# habanero-32m.net
KiCad netlist of a schematic drawn in EAGLE
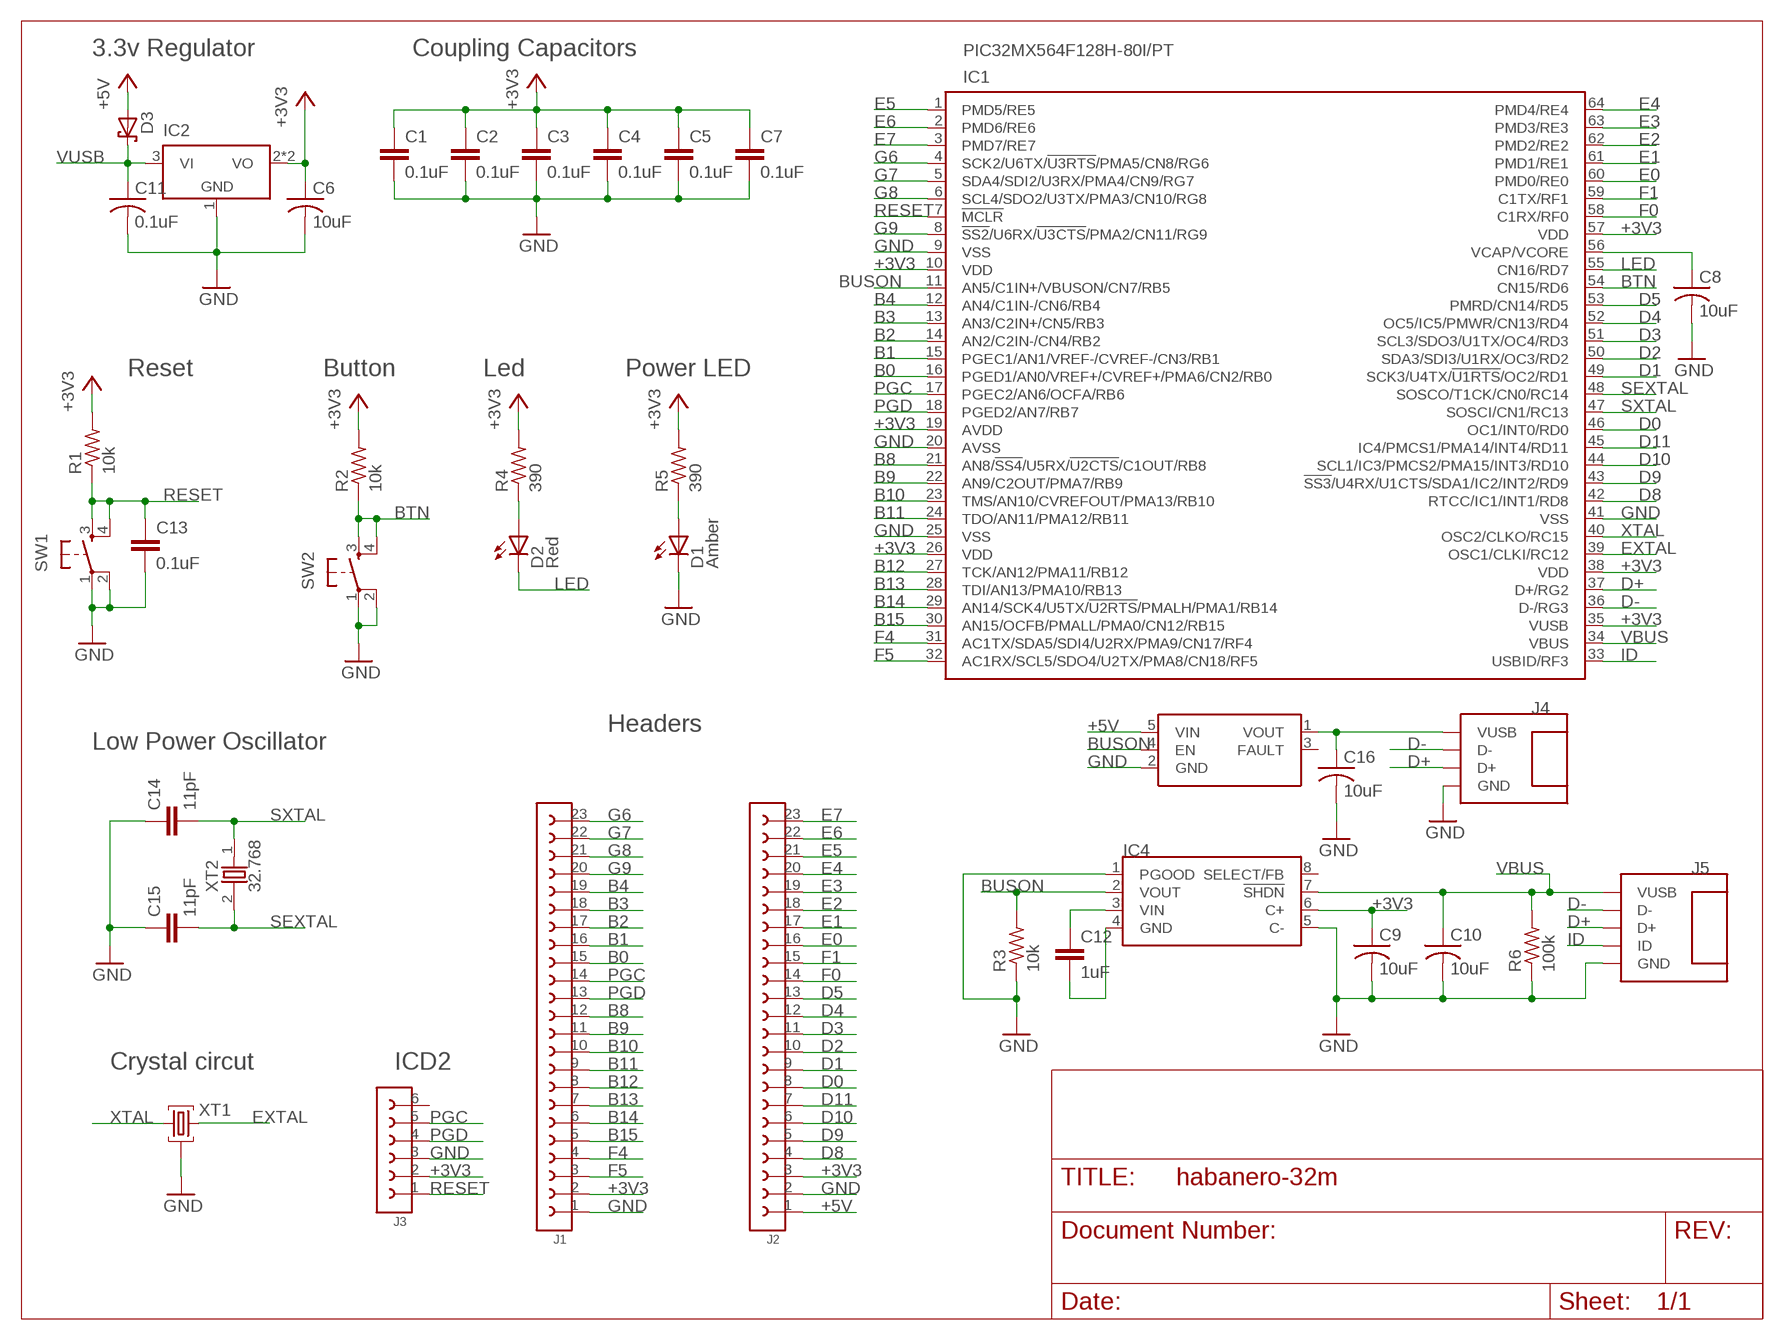
[diagram p0: schematic, sheet 1]

(export (version "E")
  (design (tool "Eeschema 10.0.6"))
  (components
    (comp (ref "C1")
      (value "0.1uF")
      (footprint "eagle-import:CAPC0603")
      (fields (field (name "MANUFACTURER") "KEMET"))
      (libsource (lib "eagle-import") (part "C?CVAC0603104Z3"))
    )
    (comp (ref "C2")
      (value "0.1uF")
      (footprint "eagle-import:CAPC0603")
      (fields (field (name "MANUFACTURER") "KEMET"))
      (libsource (lib "eagle-import") (part "C?CVAC0603104Z3"))
    )
    (comp (ref "C3")
      (value "0.1uF")
      (footprint "eagle-import:CAPC0603")
      (fields (field (name "MANUFACTURER") "KEMET"))
      (libsource (lib "eagle-import") (part "C?CVAC0603104Z3"))
    )
    (comp (ref "C4")
      (value "0.1uF")
      (footprint "eagle-import:CAPC0603")
      (fields (field (name "MANUFACTURER") "KEMET"))
      (libsource (lib "eagle-import") (part "C?CVAC0603104Z3"))
    )
    (comp (ref "C5")
      (value "0.1uF")
      (footprint "eagle-import:CAPC0603")
      (fields (field (name "MANUFACTURER") "KEMET"))
      (libsource (lib "eagle-import") (part "C?CVAC0603104Z3"))
    )
    (comp (ref "C6")
      (value "10uF")
      (footprint "eagle-import:CAPMP3216-18")
      (fields (field (name "MANUFACTURER") "KEMET"))
      (libsource (lib "eagle-import") (part "T491?A106K016AT"))
    )
    (comp (ref "C7")
      (value "0.1uF")
      (footprint "eagle-import:CAPC0603")
      (fields (field (name "MANUFACTURER") "KEMET"))
      (libsource (lib "eagle-import") (part "C?CVAC0603104Z3"))
    )
    (comp (ref "C8")
      (value "10uF")
      (footprint "eagle-import:CAPMP3216-18")
      (fields (field (name "MANUFACTURER") "KEMET"))
      (libsource (lib "eagle-import") (part "T491?A106K016AT"))
    )
    (comp (ref "C9")
      (value "10uF")
      (footprint "eagle-import:CAPMP3216-18")
      (fields (field (name "MANUFACTURER") "KEMET"))
      (libsource (lib "eagle-import") (part "T491?A106K016AT"))
    )
    (comp (ref "C10")
      (value "10uF")
      (footprint "eagle-import:CAPMP3216-18")
      (fields (field (name "MANUFACTURER") "KEMET"))
      (libsource (lib "eagle-import") (part "T491?A106K016AT"))
    )
    (comp (ref "C11")
      (value "0.1uF")
      (footprint "eagle-import:CAPMP3216-18")
      (fields (field (name "MANUFACTURER") "KEMET"))
      (libsource (lib "eagle-import") (part "T491?A104K050AT"))
    )
    (comp (ref "C12")
      (value "1uF")
      (footprint "eagle-import:CAPC0805")
      (fields (field (name "EAGLEUP") "CAPC0805"))
      (libsource (lib "eagle-import") (part "C?CRAC0805105K4"))
    )
    (comp (ref "C13")
      (value "0.1uF")
      (footprint "eagle-import:CAPC0603")
      (fields (field (name "MANUFACTURER") "KEMET"))
      (libsource (lib "eagle-import") (part "C?CVAC0603104Z3"))
    )
    (comp (ref "C14")
      (value "11pF")
      (footprint "eagle-import:CAPC0603")
      (fields (field (name "MANUFACTURER") "KEMET"))
      (libsource (lib "eagle-import") (part "C?CGAC0603110J5"))
    )
    (comp (ref "C15")
      (value "11pF")
      (footprint "eagle-import:CAPC0603")
      (fields (field (name "MANUFACTURER") "KEMET"))
      (libsource (lib "eagle-import") (part "C?CGAC0603110J5"))
    )
    (comp (ref "C16")
      (value "10uF")
      (footprint "eagle-import:CAPMP3216-18")
      (description "Capacitores de tantalio - SMD sólido 16volt 10uF 10% Lead Free")
      (fields
        (field (name "MANUFACTURER") "KEMET")
        (field (name "AVRG-PRICE") "0.18")
        (field (name "DIGIKEY") "399-8269-2-ND")
        (field (name "EAGLEUP") "CAPMP3216-18")
        (field (name "MANUFACTURER_1") "KEMET")
        (field (name "MOUSER") "80-T491A106K016")
        (field (name "OCTOPART-LINK") "http://octopart.com/t491a106k016at-kemet-145880")
      )
      (libsource (lib "eagle-import") (part "T491?A106K016AT"))
    )
    (comp (ref "D1")
      (value "Amber")
      (footprint "eagle-import:D0805")
      (libsource (lib "eagle-import") (part "SM0805AC"))
    )
    (comp (ref "D2")
      (value "Red")
      (footprint "eagle-import:D0805")
      (libsource (lib "eagle-import") (part "SM0805HC"))
    )
    (comp (ref "D3")
      (value "MBR0530T1G")
      (footprint "eagle-import:SOT123160X270-2N")
      (fields (field (name "EAGLEUP") "SOD123"))
      (libsource (lib "eagle-import") (part "MBR0530TG1"))
    )
    (comp (ref "IC1")
      (value "PIC32MX564F128H-80I/PT")
      (footprint "eagle-import:QFP50P1200X1200X100-64N")
      (libsource (lib "eagle-import") (part "PIC32MX5H?-80I/PT64F128"))
    )
    (comp (ref "IC2")
      (value "LD1117S33TR")
      (footprint "eagle-import:SOT230P700X180-4N")
      (fields (field (name "MANUFACTURER") "ST"))
      (libsource (lib "eagle-import") (part "LD1117?S33TR"))
    )
    (comp (ref "IC3")
      (value "SMTPS2141STR")
      (footprint "eagle-import:SOT95P280X100-5M")
      (fields (field (name "EAGLEUP") "SOT95P280X100-5N"))
      (libsource (lib "eagle-import") (part "SMTPS21?TRS41"))
    )
    (comp (ref "IC4")
      (value "MCP1253-33X50I/MS")
      (footprint "eagle-import:SOP65P490X109-8M")
      (fields (field (name "MANUFACTURER") "MICROCHIP"))
      (libsource (lib "eagle-import") (part "MCP125?I/MS3-33X50"))
    )
    (comp (ref "J1")
      (value "61302311121")
      (footprint "eagle-import:PHSP254P5842X254X1154-23S")
      (libsource (lib "eagle-import") (part "6130231?1121"))
    )
    (comp (ref "J2")
      (value "61302311121")
      (footprint "eagle-import:PHSP254P5842X254X1154-23S")
      (libsource (lib "eagle-import") (part "6130231?1121"))
    )
    (comp (ref "J3")
      (value "61300611121")
      (footprint "eagle-import:PHSP254P1524X254X1154-6S")
      (fields (field (name "MANUFACTURER") "WURTH"))
      (libsource (lib "eagle-import") (part "6130061?1121"))
    )
    (comp (ref "J4")
      (value "292303-1")
      (footprint "eagle-import:USB-A")
      (libsource (lib "eagle-import") (part "292303-?1"))
    )
    (comp (ref "J5")
      (value "1981584-1")
      (footprint "eagle-import:USB-MICRO-B")
      (libsource (lib "eagle-import") (part "1981584-1"))
    )
    (comp (ref "R1")
      (value "10k")
      (footprint "eagle-import:RESC0603")
      (libsource (lib "eagle-import") (part "CRG?0603F10K10"))
    )
    (comp (ref "R2")
      (value "10k")
      (footprint "eagle-import:RESC0603")
      (libsource (lib "eagle-import") (part "CRG?0603F10K10"))
    )
    (comp (ref "R3")
      (value "10k")
      (footprint "eagle-import:RESC0603")
      (libsource (lib "eagle-import") (part "CRG?0603F10K10"))
    )
    (comp (ref "R4")
      (value "390")
      (footprint "eagle-import:RESC0603")
      (libsource (lib "eagle-import") (part "CRG?0603F390R"))
    )
    (comp (ref "R5")
      (value "390")
      (footprint "eagle-import:RESC0603")
      (libsource (lib "eagle-import") (part "CRG?0603F390R"))
    )
    (comp (ref "R6")
      (value "100k")
      (footprint "eagle-import:RESC0603")
      (libsource (lib "eagle-import") (part "CRG?0603F100K"))
    )
    (comp (ref "SW1")
      (value "TL3301NF160QJ")
      (footprint "eagle-import:TACT600X600-4J")
      (fields (field (name "MANUFACTURER") "E-SWITCH"))
      (libsource (lib "eagle-import") (part "TL3301?JNF160Q"))
    )
    (comp (ref "SW2")
      (value "TL3301NF160QJ")
      (footprint "eagle-import:TACT600X600-4J")
      (fields (field (name "MANUFACTURER") "E-SWITCH"))
      (libsource (lib "eagle-import") (part "TL3301?JNF160Q"))
    )
    (comp (ref "XT1")
      (value "AWSCR-12.00CR-C")
      (footprint "eagle-import:CERAMIC460X200-3N")
      (fields (field (name "MANUFACTURER") "ABRACON"))
      (libsource (lib "eagle-import") (part "AWSCR-CR-C12.00"))
    )
    (comp (ref "XT2")
      (value "32.768")
      (footprint "eagle-import:CEMIC320X150-2N")
      (fields (field (name "MANUFACTURER") "ABRACON"))
      (libsource (lib "eagle-import") (part "ABS07-120-32.768KHZ-T"))
    )
  )
  (nets
    (net (code "1") (name "+3V3") (class "Default")
      (node (ref "C1") (pin "1") (pinfunction "1_1") (pintype "passive"))
      (node (ref "C2") (pin "1") (pinfunction "1_1") (pintype "passive"))
      (node (ref "C3") (pin "1") (pinfunction "1_1") (pintype "passive"))
      (node (ref "C4") (pin "1") (pinfunction "1_1") (pintype "passive"))
      (node (ref "C5") (pin "1") (pinfunction "1_1") (pintype "passive"))
      (node (ref "C6") (pin "1") (pinfunction "1_1") (pintype "passive"))
      (node (ref "C7") (pin "1") (pinfunction "1_1") (pintype "passive"))
      (node (ref "C9") (pin "1") (pinfunction "1_1") (pintype "passive"))
      (node (ref "IC1") (pin "10") (pinfunction "VDD_10") (pintype "power_in"))
      (node (ref "IC1") (pin "19") (pinfunction "AVDD_19") (pintype "power_in"))
      (node (ref "IC1") (pin "26") (pinfunction "VDD_26") (pintype "power_in"))
      (node (ref "IC1") (pin "35") (pinfunction "VUSB_35") (pintype "power_in"))
      (node (ref "IC1") (pin "38") (pinfunction "VDD_38") (pintype "power_in"))
      (node (ref "IC1") (pin "57") (pinfunction "VDD_57") (pintype "power_in"))
      (node (ref "IC2") (pin "2") (pinfunction "VO_2") (pintype "input"))
      (node (ref "IC2") (pin "4") (pinfunction "VO_4") (pintype "input"))
      (node (ref "IC4") (pin "6") (pinfunction "C+_6") (pintype "bidirectional"))
      (node (ref "J1") (pin "2") (pinfunction "2_2") (pintype "passive"))
      (node (ref "J2") (pin "3") (pinfunction "3_3") (pintype "passive"))
      (node (ref "J3") (pin "2") (pinfunction "2_2") (pintype "passive"))
      (node (ref "R1") (pin "P$2") (pinfunction "2_P$2") (pintype "passive"))
      (node (ref "R2") (pin "P$2") (pinfunction "2_P$2") (pintype "passive"))
      (node (ref "R4") (pin "P$2") (pinfunction "2_P$2") (pintype "passive"))
      (node (ref "R5") (pin "P$2") (pinfunction "2_P$2") (pintype "passive"))
    )
    (net (code "2") (name "+5V") (class "Default")
      (node (ref "D3") (pin "1") (pinfunction "A_1") (pintype "passive"))
      (node (ref "IC3") (pin "5") (pinfunction "VIN_5") (pintype "power_in"))
      (node (ref "J2") (pin "1") (pinfunction "1_1") (pintype "passive"))
    )
    (net (code "3") (name "/B0") (class "Default")
      (node (ref "IC1") (pin "16") (pinfunction "PGED1/AN0/VREF+/CVREF+/PMA6/CN2/RB0_16") (pintype "bidirectional"))
      (node (ref "J1") (pin "15") (pinfunction "15_15") (pintype "passive"))
    )
    (net (code "4") (name "/B1") (class "Default")
      (node (ref "IC1") (pin "15") (pinfunction "PGEC1/AN1/VREF-/CVREF-/CN3/RB1_15") (pintype "bidirectional"))
      (node (ref "J1") (pin "16") (pinfunction "16_16") (pintype "passive"))
    )
    (net (code "5") (name "/B2") (class "Default")
      (node (ref "IC1") (pin "14") (pinfunction "AN2/C2IN-/CN4/RB2_14") (pintype "bidirectional"))
      (node (ref "J1") (pin "17") (pinfunction "17_17") (pintype "passive"))
    )
    (net (code "6") (name "/B3") (class "Default")
      (node (ref "IC1") (pin "13") (pinfunction "AN3/C2IN+/CN5/RB3_13") (pintype "bidirectional"))
      (node (ref "J1") (pin "18") (pinfunction "18_18") (pintype "passive"))
    )
    (net (code "7") (name "/B4") (class "Default")
      (node (ref "IC1") (pin "12") (pinfunction "AN4/C1IN-/CN6/RB4_12") (pintype "bidirectional"))
      (node (ref "J1") (pin "19") (pinfunction "19_19") (pintype "passive"))
    )
    (net (code "8") (name "/B8") (class "Default")
      (node (ref "IC1") (pin "21") (pinfunction "AN8/~{SS4}/U5RX/~{U2CTS}/C1OUT/RB8_21") (pintype "bidirectional"))
      (node (ref "J1") (pin "12") (pinfunction "12_12") (pintype "passive"))
    )
    (net (code "9") (name "/B9") (class "Default")
      (node (ref "IC1") (pin "22") (pinfunction "AN9/C2OUT/PMA7/RB9_22") (pintype "bidirectional"))
      (node (ref "J1") (pin "11") (pinfunction "11_11") (pintype "passive"))
    )
    (net (code "10") (name "/B10") (class "Default")
      (node (ref "IC1") (pin "23") (pinfunction "TMS/AN10/CVREFOUT/PMA13/RB10_23") (pintype "bidirectional"))
      (node (ref "J1") (pin "10") (pinfunction "10_10") (pintype "passive"))
    )
    (net (code "11") (name "/B11") (class "Default")
      (node (ref "IC1") (pin "24") (pinfunction "TDO/AN11/PMA12/RB11_24") (pintype "bidirectional"))
      (node (ref "J1") (pin "9") (pinfunction "9_9") (pintype "passive"))
    )
    (net (code "12") (name "/B12") (class "Default")
      (node (ref "IC1") (pin "27") (pinfunction "TCK/AN12/PMA11/RB12_27") (pintype "bidirectional"))
      (node (ref "J1") (pin "8") (pinfunction "8_8") (pintype "passive"))
    )
    (net (code "13") (name "/B13") (class "Default")
      (node (ref "IC1") (pin "28") (pinfunction "TDI/AN13/PMA10/RB13_28") (pintype "bidirectional"))
      (node (ref "J1") (pin "7") (pinfunction "7_7") (pintype "passive"))
    )
    (net (code "14") (name "/B14") (class "Default")
      (node (ref "IC1") (pin "29") (pinfunction "AN14/SCK4/U5TX/~{U2RTS}/PMALH/PMA1/RB14_29") (pintype "bidirectional"))
      (node (ref "J1") (pin "6") (pinfunction "6_6") (pintype "passive"))
    )
    (net (code "15") (name "/B15") (class "Default")
      (node (ref "IC1") (pin "30") (pinfunction "AN15/OCFB/PMALL/PMA0/CN12/RB15_30") (pintype "bidirectional"))
      (node (ref "J1") (pin "5") (pinfunction "5_5") (pintype "passive"))
    )
    (net (code "16") (name "/BTN") (class "Default")
      (node (ref "IC1") (pin "54") (pinfunction "CN15/RD6_54") (pintype "bidirectional"))
      (node (ref "R2") (pin "P$1") (pinfunction "1_P$1") (pintype "passive"))
      (node (ref "SW2") (pin "3") (pinfunction "S_3") (pintype "passive"))
      (node (ref "SW2") (pin "4") (pinfunction "S1_4") (pintype "passive"))
    )
    (net (code "17") (name "/BUSON") (class "Default")
      (node (ref "IC1") (pin "11") (pinfunction "AN5/C1IN+/VBUSON/CN7/RB5_11") (pintype "bidirectional"))
      (node (ref "IC3") (pin "4") (pinfunction "EN_4") (pintype "bidirectional"))
      (node (ref "IC4") (pin "2") (pinfunction "VOUT_2") (pintype "bidirectional"))
      (node (ref "R3") (pin "P$2") (pinfunction "2_P$2") (pintype "passive"))
    )
    (net (code "18") (name "/D+") (class "Default")
      (node (ref "IC1") (pin "37") (pinfunction "D+/RG2_37") (pintype "bidirectional"))
      (node (ref "J4") (pin "2") (pinfunction "D+_2") (pintype "bidirectional"))
      (node (ref "J5") (pin "3") (pinfunction "D+_3") (pintype "bidirectional"))
    )
    (net (code "19") (name "/D-") (class "Default")
      (node (ref "IC1") (pin "36") (pinfunction "D-/RG3_36") (pintype "bidirectional"))
      (node (ref "J4") (pin "3") (pinfunction "D-_3") (pintype "bidirectional"))
      (node (ref "J5") (pin "2") (pinfunction "D-_2") (pintype "bidirectional"))
    )
    (net (code "20") (name "/D0") (class "Default")
      (node (ref "IC1") (pin "46") (pinfunction "OC1/INT0/RD0_46") (pintype "bidirectional"))
      (node (ref "J2") (pin "8") (pinfunction "8_8") (pintype "passive"))
    )
    (net (code "21") (name "/D1") (class "Default")
      (node (ref "IC1") (pin "49") (pinfunction "SCK3/U4TX/~{U1RTS}/OC2/RD1_49") (pintype "bidirectional"))
      (node (ref "J2") (pin "9") (pinfunction "9_9") (pintype "passive"))
    )
    (net (code "22") (name "/D2") (class "Default")
      (node (ref "IC1") (pin "50") (pinfunction "SDA3/SDI3/U1RX/OC3/RD2_50") (pintype "bidirectional"))
      (node (ref "J2") (pin "10") (pinfunction "10_10") (pintype "passive"))
    )
    (net (code "23") (name "/D3") (class "Default")
      (node (ref "IC1") (pin "51") (pinfunction "SCL3/SDO3/U1TX/OC4/RD3_51") (pintype "bidirectional"))
      (node (ref "J2") (pin "11") (pinfunction "11_11") (pintype "passive"))
    )
    (net (code "24") (name "/D4") (class "Default")
      (node (ref "IC1") (pin "52") (pinfunction "OC5/IC5/PMWR/CN13/RD4_52") (pintype "bidirectional"))
      (node (ref "J2") (pin "12") (pinfunction "12_12") (pintype "passive"))
    )
    (net (code "25") (name "/D5") (class "Default")
      (node (ref "IC1") (pin "53") (pinfunction "PMRD/CN14/RD5_53") (pintype "bidirectional"))
      (node (ref "J2") (pin "13") (pinfunction "13_13") (pintype "passive"))
    )
    (net (code "26") (name "/D8") (class "Default")
      (node (ref "IC1") (pin "42") (pinfunction "RTCC/IC1/INT1/RD8_42") (pintype "bidirectional"))
      (node (ref "J2") (pin "4") (pinfunction "4_4") (pintype "passive"))
    )
    (net (code "27") (name "/D9") (class "Default")
      (node (ref "IC1") (pin "43") (pinfunction "~{SS3}/U4RX/U1CTS/SDA1/IC2/INT2/RD9_43") (pintype "bidirectional"))
      (node (ref "J2") (pin "5") (pinfunction "5_5") (pintype "passive"))
    )
    (net (code "28") (name "/D10") (class "Default")
      (node (ref "IC1") (pin "44") (pinfunction "SCL1/IC3/PMCS2/PMA15/INT3/RD10_44") (pintype "bidirectional"))
      (node (ref "J2") (pin "6") (pinfunction "6_6") (pintype "passive"))
    )
    (net (code "29") (name "/D11") (class "Default")
      (node (ref "IC1") (pin "45") (pinfunction "IC4/PMCS1/PMA14/INT4/RD11_45") (pintype "bidirectional"))
      (node (ref "J2") (pin "7") (pinfunction "7_7") (pintype "passive"))
    )
    (net (code "30") (name "/E0") (class "Default")
      (node (ref "IC1") (pin "60") (pinfunction "PMD0/RE0_60") (pintype "bidirectional"))
      (node (ref "J2") (pin "16") (pinfunction "16_16") (pintype "passive"))
    )
    (net (code "31") (name "/E1") (class "Default")
      (node (ref "IC1") (pin "61") (pinfunction "PMD1/RE1_61") (pintype "bidirectional"))
      (node (ref "J2") (pin "17") (pinfunction "17_17") (pintype "passive"))
    )
    (net (code "32") (name "/E2") (class "Default")
      (node (ref "IC1") (pin "62") (pinfunction "PMD2/RE2_62") (pintype "bidirectional"))
      (node (ref "J2") (pin "18") (pinfunction "18_18") (pintype "passive"))
    )
    (net (code "33") (name "/E3") (class "Default")
      (node (ref "IC1") (pin "63") (pinfunction "PMD3/RE3_63") (pintype "bidirectional"))
      (node (ref "J2") (pin "19") (pinfunction "19_19") (pintype "passive"))
    )
    (net (code "34") (name "/E4") (class "Default")
      (node (ref "IC1") (pin "64") (pinfunction "PMD4/RE4_64") (pintype "bidirectional"))
      (node (ref "J2") (pin "20") (pinfunction "20_20") (pintype "passive"))
    )
    (net (code "35") (name "/E5") (class "Default")
      (node (ref "IC1") (pin "1") (pinfunction "PMD5/RE5_1") (pintype "bidirectional"))
      (node (ref "J2") (pin "21") (pinfunction "21_21") (pintype "passive"))
    )
    (net (code "36") (name "/E6") (class "Default")
      (node (ref "IC1") (pin "2") (pinfunction "PMD6/RE6_2") (pintype "bidirectional"))
      (node (ref "J2") (pin "22") (pinfunction "22_22") (pintype "passive"))
    )
    (net (code "37") (name "/E7") (class "Default")
      (node (ref "IC1") (pin "3") (pinfunction "PMD7/RE7_3") (pintype "bidirectional"))
      (node (ref "J2") (pin "23") (pinfunction "23_23") (pintype "passive"))
    )
    (net (code "38") (name "/EXTAL") (class "Default")
      (node (ref "IC1") (pin "39") (pinfunction "OSC1/CLKI/RC12_39") (pintype "bidirectional"))
      (node (ref "XT1") (pin "3") (pinfunction "3_3") (pintype "passive"))
    )
    (net (code "39") (name "/F0") (class "Default")
      (node (ref "IC1") (pin "58") (pinfunction "C1RX/RF0_58") (pintype "bidirectional"))
      (node (ref "J2") (pin "14") (pinfunction "14_14") (pintype "passive"))
    )
    (net (code "40") (name "/F1") (class "Default")
      (node (ref "IC1") (pin "59") (pinfunction "C1TX/RF1_59") (pintype "bidirectional"))
      (node (ref "J2") (pin "15") (pinfunction "15_15") (pintype "passive"))
    )
    (net (code "41") (name "/F4") (class "Default")
      (node (ref "IC1") (pin "31") (pinfunction "AC1TX/SDA5/SDI4/U2RX/PMA9/CN17/RF4_31") (pintype "bidirectional"))
      (node (ref "J1") (pin "4") (pinfunction "4_4") (pintype "passive"))
    )
    (net (code "42") (name "/F5") (class "Default")
      (node (ref "IC1") (pin "32") (pinfunction "AC1RX/SCL5/SDO4/U2TX/PMA8/CN18/RF5_32") (pintype "bidirectional"))
      (node (ref "J1") (pin "3") (pinfunction "3_3") (pintype "passive"))
    )
    (net (code "43") (name "/G6") (class "Default")
      (node (ref "IC1") (pin "4") (pinfunction "SCK2/U6TX/~{U3RTS}/PMA5/CN8/RG6_4") (pintype "bidirectional"))
      (node (ref "J1") (pin "23") (pinfunction "23_23") (pintype "passive"))
    )
    (net (code "44") (name "/G7") (class "Default")
      (node (ref "IC1") (pin "5") (pinfunction "SDA4/SDI2/U3RX/PMA4/CN9/RG7_5") (pintype "bidirectional"))
      (node (ref "J1") (pin "22") (pinfunction "22_22") (pintype "passive"))
    )
    (net (code "45") (name "/G8") (class "Default")
      (node (ref "IC1") (pin "6") (pinfunction "SCL4/SDO2/U3TX/PMA3/CN10/RG8_6") (pintype "bidirectional"))
      (node (ref "J1") (pin "21") (pinfunction "21_21") (pintype "passive"))
    )
    (net (code "46") (name "/G9") (class "Default")
      (node (ref "IC1") (pin "8") (pinfunction "~{SS2}/U6RX/~{U3CTS}/PMA2/CN11/RG9_8") (pintype "bidirectional"))
      (node (ref "J1") (pin "20") (pinfunction "20_20") (pintype "passive"))
    )
    (net (code "47") (name "/ID") (class "Default")
      (node (ref "IC1") (pin "33") (pinfunction "USBID/RF3_33") (pintype "bidirectional"))
      (node (ref "J5") (pin "4") (pinfunction "ID_4") (pintype "bidirectional"))
    )
    (net (code "48") (name "/LED") (class "Default")
      (node (ref "D2") (pin "2") (pinfunction "C_2") (pintype "passive"))
      (node (ref "IC1") (pin "55") (pinfunction "CN16/RD7_55") (pintype "bidirectional"))
    )
    (net (code "49") (name "/PGC") (class "Default")
      (node (ref "IC1") (pin "17") (pinfunction "PGEC2/AN6/OCFA/RB6_17") (pintype "bidirectional"))
      (node (ref "J1") (pin "14") (pinfunction "14_14") (pintype "passive"))
      (node (ref "J3") (pin "5") (pinfunction "5_5") (pintype "passive"))
    )
    (net (code "50") (name "/PGD") (class "Default")
      (node (ref "IC1") (pin "18") (pinfunction "PGED2/AN7/RB7_18") (pintype "bidirectional"))
      (node (ref "J1") (pin "13") (pinfunction "13_13") (pintype "passive"))
      (node (ref "J3") (pin "4") (pinfunction "4_4") (pintype "passive"))
    )
    (net (code "51") (name "/RESET") (class "Default")
      (node (ref "C13") (pin "1") (pinfunction "1_1") (pintype "passive"))
      (node (ref "IC1") (pin "7") (pinfunction "~{MCLR}_7") (pintype "bidirectional"))
      (node (ref "J3") (pin "1") (pinfunction "1_1") (pintype "passive"))
      (node (ref "R1") (pin "P$1") (pinfunction "1_P$1") (pintype "passive"))
      (node (ref "SW1") (pin "3") (pinfunction "S_3") (pintype "passive"))
      (node (ref "SW1") (pin "4") (pinfunction "S1_4") (pintype "passive"))
    )
    (net (code "52") (name "/SEXTAL") (class "Default")
      (node (ref "C15") (pin "2") (pinfunction "2_2") (pintype "passive"))
      (node (ref "IC1") (pin "48") (pinfunction "SOSCO/T1CK/CN0/RC14_48") (pintype "bidirectional"))
      (node (ref "XT2") (pin "2") (pinfunction "1_2") (pintype "passive"))
    )
    (net (code "53") (name "/SXTAL") (class "Default")
      (node (ref "C14") (pin "2") (pinfunction "2_2") (pintype "passive"))
      (node (ref "IC1") (pin "47") (pinfunction "SOSCI/CN1/RC13_47") (pintype "bidirectional"))
      (node (ref "XT2") (pin "1") (pinfunction "2_1") (pintype "passive"))
    )
    (net (code "54") (name "/VBUS") (class "Default")
      (node (ref "C10") (pin "1") (pinfunction "1_1") (pintype "passive"))
      (node (ref "IC1") (pin "34") (pinfunction "VBUS_34") (pintype "power_in"))
      (node (ref "IC4") (pin "7") (pinfunction "~{SHDN}_7") (pintype "bidirectional"))
      (node (ref "J5") (pin "1") (pinfunction "VUSB_1") (pintype "bidirectional"))
      (node (ref "R6") (pin "P$2") (pinfunction "2_P$2") (pintype "passive"))
    )
    (net (code "55") (name "/VUSB") (class "Default")
      (node (ref "C11") (pin "1") (pinfunction "1_1") (pintype "passive"))
      (node (ref "D3") (pin "2") (pinfunction "C_2") (pintype "passive"))
      (node (ref "IC2") (pin "3") (pinfunction "VI_3") (pintype "input"))
    )
    (net (code "56") (name "/XTAL") (class "Default")
      (node (ref "IC1") (pin "40") (pinfunction "OSC2/CLKO/RC15_40") (pintype "bidirectional"))
      (node (ref "XT1") (pin "1") (pinfunction "1_1") (pintype "passive"))
    )
    (net (code "57") (name "GND") (class "Default")
      (node (ref "C1") (pin "2") (pinfunction "2_2") (pintype "passive"))
      (node (ref "C10") (pin "2") (pinfunction "2_2") (pintype "passive"))
      (node (ref "C11") (pin "2") (pinfunction "2_2") (pintype "passive"))
      (node (ref "C13") (pin "2") (pinfunction "2_2") (pintype "passive"))
      (node (ref "C14") (pin "1") (pinfunction "1_1") (pintype "passive"))
      (node (ref "C15") (pin "1") (pinfunction "1_1") (pintype "passive"))
      (node (ref "C16") (pin "2") (pinfunction "2_2") (pintype "passive"))
      (node (ref "C2") (pin "2") (pinfunction "2_2") (pintype "passive"))
      (node (ref "C3") (pin "2") (pinfunction "2_2") (pintype "passive"))
      (node (ref "C4") (pin "2") (pinfunction "2_2") (pintype "passive"))
      (node (ref "C5") (pin "2") (pinfunction "2_2") (pintype "passive"))
      (node (ref "C6") (pin "2") (pinfunction "2_2") (pintype "passive"))
      (node (ref "C7") (pin "2") (pinfunction "2_2") (pintype "passive"))
      (node (ref "C8") (pin "2") (pinfunction "2_2") (pintype "passive"))
      (node (ref "C9") (pin "2") (pinfunction "2_2") (pintype "passive"))
      (node (ref "D1") (pin "2") (pinfunction "C_2") (pintype "passive"))
      (node (ref "IC1") (pin "20") (pinfunction "AVSS_20") (pintype "power_in"))
      (node (ref "IC1") (pin "25") (pinfunction "VSS_25") (pintype "power_in"))
      (node (ref "IC1") (pin "41") (pinfunction "VSS_41") (pintype "power_in"))
      (node (ref "IC1") (pin "9") (pinfunction "VSS_9") (pintype "power_in"))
      (node (ref "IC2") (pin "1") (pinfunction "GND_1") (pintype "power_in"))
      (node (ref "IC3") (pin "2") (pinfunction "GND_2") (pintype "power_in"))
      (node (ref "IC4") (pin "1") (pinfunction "PGOOD_1") (pintype "bidirectional"))
      (node (ref "IC4") (pin "5") (pinfunction "C-_5") (pintype "bidirectional"))
      (node (ref "J1") (pin "1") (pinfunction "1_1") (pintype "passive"))
      (node (ref "J2") (pin "2") (pinfunction "2_2") (pintype "passive"))
      (node (ref "J3") (pin "3") (pinfunction "3_3") (pintype "passive"))
      (node (ref "J4") (pin "4") (pinfunction "GND_4") (pintype "bidirectional"))
      (node (ref "J5") (pin "5") (pinfunction "GND_5") (pintype "bidirectional"))
      (node (ref "R3") (pin "P$1") (pinfunction "1_P$1") (pintype "passive"))
      (node (ref "R6") (pin "P$1") (pinfunction "1_P$1") (pintype "passive"))
      (node (ref "SW1") (pin "1") (pinfunction "P_1") (pintype "passive"))
      (node (ref "SW1") (pin "2") (pinfunction "P1_2") (pintype "passive"))
      (node (ref "SW2") (pin "1") (pinfunction "P_1") (pintype "passive"))
      (node (ref "SW2") (pin "2") (pinfunction "P1_2") (pintype "passive"))
      (node (ref "XT1") (pin "2") (pinfunction "2_2") (pintype "passive"))
    )
    (net (code "58") (name "Net-(D1-A)") (class "Default")
      (node (ref "D1") (pin "1") (pinfunction "A_1") (pintype "passive"))
      (node (ref "R5") (pin "P$1") (pinfunction "1_P$1") (pintype "passive"))
    )
    (net (code "59") (name "Net-(D2-A)") (class "Default")
      (node (ref "D2") (pin "1") (pinfunction "A_1") (pintype "passive"))
      (node (ref "R4") (pin "P$1") (pinfunction "1_P$1") (pintype "passive"))
    )
    (net (code "60") (name "Net-(IC1-VCAP{slash}VCORE)") (class "Default")
      (node (ref "C8") (pin "1") (pinfunction "1_1") (pintype "passive"))
      (node (ref "IC1") (pin "56") (pinfunction "VCAP/VCORE_56") (pintype "power_in"))
    )
    (net (code "61") (name "Net-(IC3-VOUT)") (class "Default")
      (node (ref "C16") (pin "1") (pinfunction "1_1") (pintype "passive"))
      (node (ref "IC3") (pin "1") (pinfunction "VOUT_1") (pintype "power_in"))
      (node (ref "J4") (pin "1") (pinfunction "VUSB_1") (pintype "bidirectional"))
    )
    (net (code "62") (name "Net-(IC4-GND)") (class "Default")
      (node (ref "C12") (pin "2") (pinfunction "2_2") (pintype "passive"))
      (node (ref "IC4") (pin "4") (pinfunction "GND_4") (pintype "bidirectional"))
    )
    (net (code "63") (name "Net-(IC4-VIN)") (class "Default")
      (node (ref "C12") (pin "1") (pinfunction "1_1") (pintype "passive"))
      (node (ref "IC4") (pin "3") (pinfunction "VIN_3") (pintype "bidirectional"))
    )
    (net (code "64") (name "unconnected-(IC3-FAULT-Pad3)") (class "Default")
      (node (ref "IC3") (pin "3") (pinfunction "FAULT_3") (pintype "bidirectional"))
    )
    (net (code "65") (name "unconnected-(IC4-SELECT{slash}FB-Pad8)") (class "Default")
      (node (ref "IC4") (pin "8") (pinfunction "SELECT/FB_8") (pintype "bidirectional"))
    )
    (net (code "66") (name "unconnected-(J3-Pad6)") (class "Default")
      (node (ref "J3") (pin "6") (pinfunction "6_6") (pintype "passive"))
    )
  )
)
